# BW1098OAK_IMX378.net
KiCad netlist of a schematic drawn in Altium Designer
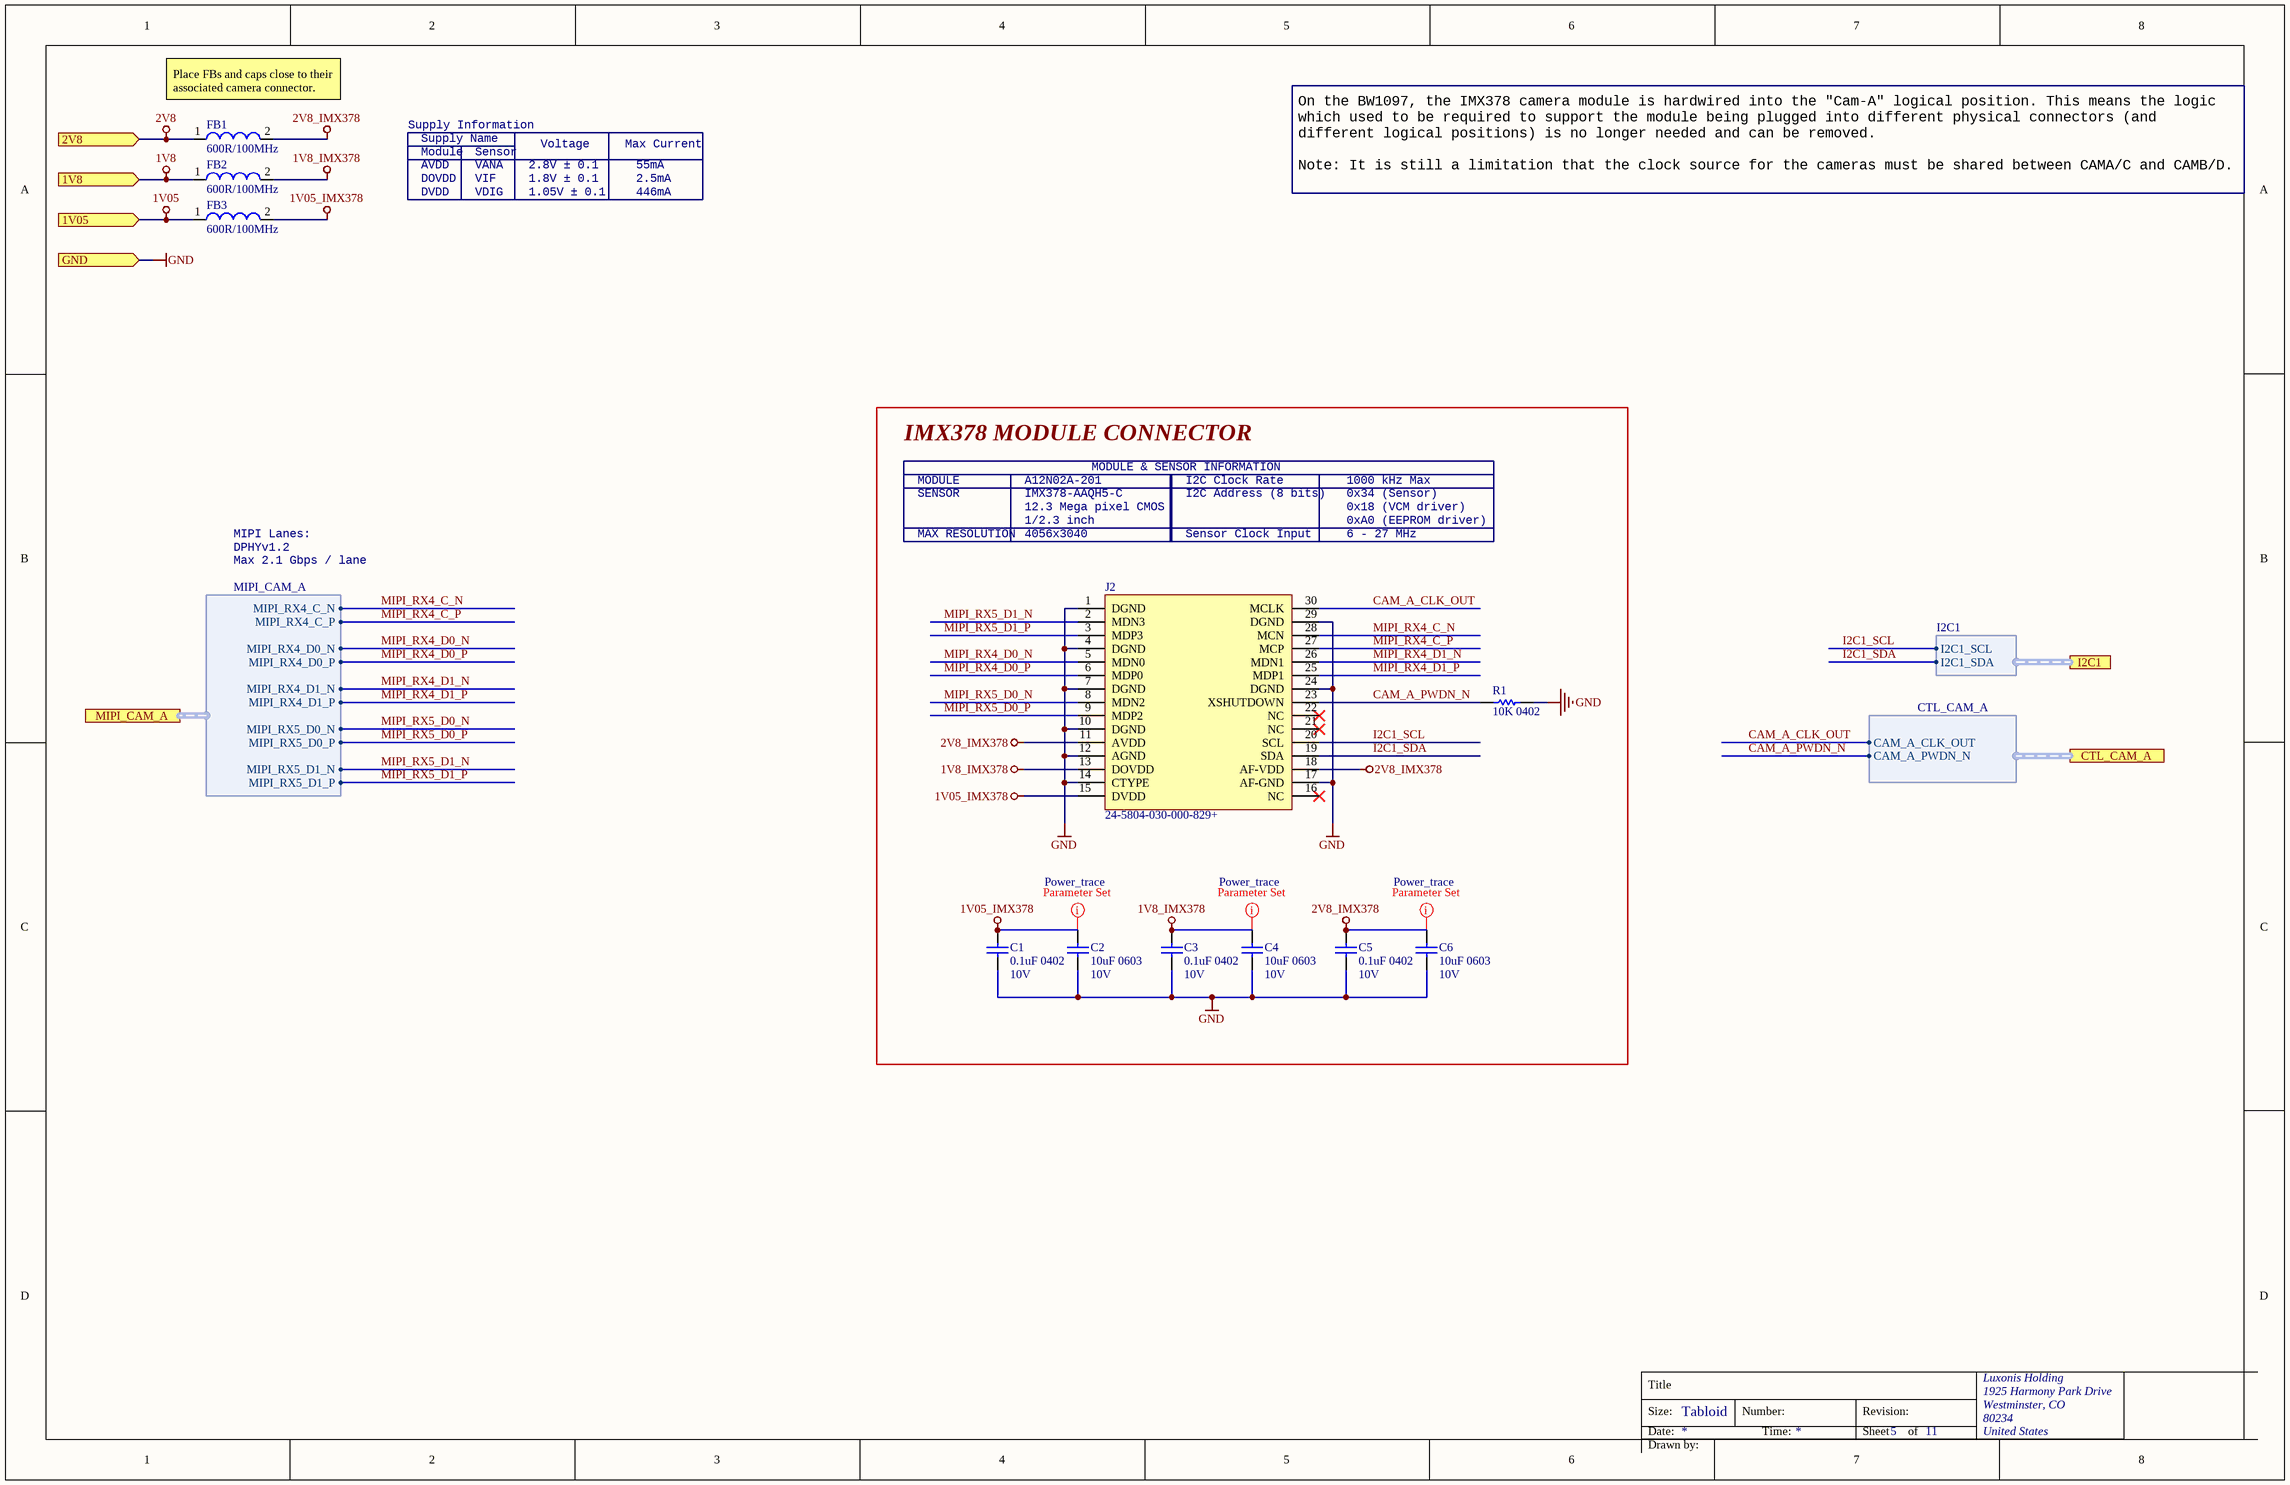
[diagram p0: BW1098OAK_IMX378.SchDoc]

(export (version "E")
  (design (tool "Eeschema 10.0.6"))
  (components
    (comp (ref "C1")
      (value "0.1uF 0402")
      (footprint "CAP_Altium_Vault_Generic:CAPC0402(1005)70_L")
      (description "CAP CER 0.1UF 10V X7R 0402 5%")
      (fields (field (name "TOLERANCE") "5%") (field (name "VOLTAGE RATING") "10V"))
      (libsource (lib "LuxonisMaster") (part "GRM155R71A104JA01D"))
    )
    (comp (ref "C2")
      (value "10uF 0603")
      (footprint "CAP_Altium_Vault_Generic:CAPC0603(1608)100_L")
      (description "CAP CER 10UF 10V X5R 0603 20%")
      (fields (field (name "TOLERANCE") "20%") (field (name "VOLTAGE RATING") "10V"))
      (libsource (lib "LuxonisMaster") (part "GRM188R61A106ME69D"))
    )
    (comp (ref "C3")
      (value "0.1uF 0402")
      (footprint "CAP_Altium_Vault_Generic:CAPC0402(1005)70_L")
      (description "CAP CER 0.1UF 10V X7R 0402 5%")
      (fields (field (name "TOLERANCE") "5%") (field (name "VOLTAGE RATING") "10V"))
      (libsource (lib "LuxonisMaster") (part "GRM155R71A104JA01D"))
    )
    (comp (ref "C4")
      (value "10uF 0603")
      (footprint "CAP_Altium_Vault_Generic:CAPC0603(1608)100_L")
      (description "CAP CER 10UF 10V X5R 0603 20%")
      (fields (field (name "TOLERANCE") "20%") (field (name "VOLTAGE RATING") "10V"))
      (libsource (lib "LuxonisMaster") (part "GRM188R61A106ME69D"))
    )
    (comp (ref "C5")
      (value "0.1uF 0402")
      (footprint "CAP_Altium_Vault_Generic:CAPC0402(1005)70_L")
      (description "CAP CER 0.1UF 10V X7R 0402 5%")
      (fields (field (name "TOLERANCE") "5%") (field (name "VOLTAGE RATING") "10V"))
      (libsource (lib "LuxonisMaster") (part "GRM155R71A104JA01D"))
    )
    (comp (ref "C6")
      (value "10uF 0603")
      (footprint "CAP_Altium_Vault_Generic:CAPC0603(1608)100_L")
      (description "CAP CER 10UF 10V X5R 0603 20%")
      (fields (field (name "TOLERANCE") "20%") (field (name "VOLTAGE RATING") "10V"))
      (libsource (lib "LuxonisMaster") (part "GRM188R61A106ME69D"))
    )
    (comp (ref "FB1")
      (value "600R/100MHz")
      (footprint "LuxonisMaster:2508056017Y2")
      (description "FERRITE BEAD, 0.1OHM, 2A, 0805, 600R/100MHz")
      (fields (field (name "TOLERANCE") "25%"))
      (libsource (lib "LuxonisMaster") (part "2508056017Y2"))
    )
    (comp (ref "FB2")
      (value "600R/100MHz")
      (footprint "LuxonisMaster:2508056017Y2")
      (description "FERRITE BEAD, 0.1OHM, 2A, 0805, 600R/100MHz")
      (fields (field (name "TOLERANCE") "25%"))
      (libsource (lib "LuxonisMaster") (part "2508056017Y2"))
    )
    (comp (ref "FB3")
      (value "600R/100MHz")
      (footprint "LuxonisMaster:2508056017Y2")
      (description "FERRITE BEAD, 0.1OHM, 2A, 0805, 600R/100MHz")
      (fields (field (name "TOLERANCE") "25%"))
      (libsource (lib "LuxonisMaster") (part "2508056017Y2"))
    )
    (comp (ref "J2")
      (value "24-5804-030-000-829+")
      (footprint "BW1098OBC_R3M1E3:A12N02A-201_1.6mmbrd_MatedModule")
      (description "CONN Series 5804 board to board 0.4mm pitch 30 way connector")
      (libsource (lib "BW1098OAK_R0M0E0") (part "A12N02A-201_Connector_(1.6mm_brd)"))
    )
    (comp (ref "R1")
      (value "10K 0402")
      (footprint "RES_Altium_Vault_Generic:RESC0402(1005)_L")
      (fields (field (name "TOLERANCE") "1%"))
      (libsource (lib "LuxonisMaster") (part "RC0402FR-1310KL"))
    )
  )
  (nets
    (net (code "4") (name "/CAM_A_CLK_OUT") (class "Default")
      (node (ref "J2") (pin "30") (pinfunction "MCLK_30") (pintype "passive"))
    )
    (net (code "5") (name "/CAM_A_PWDN_N") (class "Default")
      (node (ref "J2") (pin "23") (pinfunction "XSHUTDOWN_23") (pintype "passive"))
      (node (ref "R1") (pin "1") (pinfunction "1_1") (pintype "passive"))
    )
    (net (code "6") (name "/I2C1_SCL") (class "Default")
      (node (ref "J2") (pin "20") (pinfunction "SCL_20") (pintype "passive"))
    )
    (net (code "7") (name "/I2C1_SDA") (class "Default")
      (node (ref "J2") (pin "19") (pinfunction "SDA_19") (pintype "passive"))
    )
    (net (code "8") (name "/MIPI_RX4_C_N") (class "Default")
      (node (ref "J2") (pin "28") (pinfunction "MCN_28") (pintype "passive"))
    )
    (net (code "9") (name "/MIPI_RX4_C_P") (class "Default")
      (node (ref "J2") (pin "27") (pinfunction "MCP_27") (pintype "passive"))
    )
    (net (code "10") (name "/MIPI_RX4_D0_N") (class "Default")
      (node (ref "J2") (pin "5") (pinfunction "MDN0_5") (pintype "passive"))
    )
    (net (code "11") (name "/MIPI_RX4_D0_P") (class "Default")
      (node (ref "J2") (pin "6") (pinfunction "MDP0_6") (pintype "passive"))
    )
    (net (code "12") (name "/MIPI_RX4_D1_N") (class "Default")
      (node (ref "J2") (pin "26") (pinfunction "MDN1_26") (pintype "passive"))
    )
    (net (code "13") (name "/MIPI_RX4_D1_P") (class "Default")
      (node (ref "J2") (pin "25") (pinfunction "MDP1_25") (pintype "passive"))
    )
    (net (code "14") (name "/MIPI_RX5_D0_N") (class "Default")
      (node (ref "J2") (pin "8") (pinfunction "MDN2_8") (pintype "passive"))
    )
    (net (code "15") (name "/MIPI_RX5_D0_P") (class "Default")
      (node (ref "J2") (pin "9") (pinfunction "MDP2_9") (pintype "passive"))
    )
    (net (code "16") (name "/MIPI_RX5_D1_N") (class "Default")
      (node (ref "J2") (pin "2") (pinfunction "MDN3_2") (pintype "passive"))
    )
    (net (code "17") (name "/MIPI_RX5_D1_P") (class "Default")
      (node (ref "J2") (pin "3") (pinfunction "MDP3_3") (pintype "passive"))
    )
    (net (code "21") (name "1V05") (class "Default")
      (node (ref "FB3") (pin "1") (pinfunction "1_1") (pintype "passive"))
    )
    (net (code "22") (name "1V05_IMX378") (class "Default")
      (node (ref "C1") (pin "2") (pinfunction "2_2") (pintype "passive"))
      (node (ref "C2") (pin "2") (pinfunction "2_2") (pintype "passive"))
      (node (ref "FB3") (pin "2") (pinfunction "2_2") (pintype "passive"))
      (node (ref "J2") (pin "15") (pinfunction "DVDD_15") (pintype "passive"))
    )
    (net (code "23") (name "1V8") (class "Default")
      (node (ref "FB2") (pin "1") (pinfunction "1_1") (pintype "passive"))
    )
    (net (code "24") (name "1V8_IMX378") (class "Default")
      (node (ref "C3") (pin "2") (pinfunction "2_2") (pintype "passive"))
      (node (ref "C4") (pin "2") (pinfunction "2_2") (pintype "passive"))
      (node (ref "FB2") (pin "2") (pinfunction "2_2") (pintype "passive"))
      (node (ref "J2") (pin "13") (pinfunction "DOVDD_13") (pintype "passive"))
    )
    (net (code "25") (name "2V8") (class "Default")
      (node (ref "FB1") (pin "1") (pinfunction "1_1") (pintype "passive"))
    )
    (net (code "26") (name "2V8_IMX378") (class "Default")
      (node (ref "C5") (pin "2") (pinfunction "2_2") (pintype "passive"))
      (node (ref "C6") (pin "2") (pinfunction "2_2") (pintype "passive"))
      (node (ref "FB1") (pin "2") (pinfunction "2_2") (pintype "passive"))
      (node (ref "J2") (pin "11") (pinfunction "AVDD_11") (pintype "passive"))
      (node (ref "J2") (pin "18") (pinfunction "AF-VDD_18") (pintype "passive"))
    )
    (net (code "27") (name "GND") (class "Default")
      (node (ref "C1") (pin "1") (pinfunction "1_1") (pintype "passive"))
      (node (ref "C2") (pin "1") (pinfunction "1_1") (pintype "passive"))
      (node (ref "C3") (pin "1") (pinfunction "1_1") (pintype "passive"))
      (node (ref "C4") (pin "1") (pinfunction "1_1") (pintype "passive"))
      (node (ref "C5") (pin "1") (pinfunction "1_1") (pintype "passive"))
      (node (ref "C6") (pin "1") (pinfunction "1_1") (pintype "passive"))
      (node (ref "J2") (pin "1") (pinfunction "DGND_1") (pintype "passive"))
      (node (ref "J2") (pin "10") (pinfunction "DGND_10") (pintype "passive"))
      (node (ref "J2") (pin "12") (pinfunction "AGND_12") (pintype "passive"))
      (node (ref "J2") (pin "14") (pinfunction "CTYPE_14") (pintype "passive"))
      (node (ref "J2") (pin "17") (pinfunction "AF-GND_17") (pintype "passive"))
      (node (ref "J2") (pin "24") (pinfunction "DGND_24") (pintype "passive"))
      (node (ref "J2") (pin "29") (pinfunction "DGND_29") (pintype "passive"))
      (node (ref "J2") (pin "4") (pinfunction "DGND_4") (pintype "passive"))
      (node (ref "J2") (pin "7") (pinfunction "DGND_7") (pintype "passive"))
      (node (ref "R1") (pin "2") (pinfunction "2_2") (pintype "passive"))
    )
    (net (code "28") (name "unconnected-(J2-NC-Pad16)") (class "Default")
      (node (ref "J2") (pin "16") (pinfunction "NC_16") (pintype "passive+no_connect"))
    )
    (net (code "29") (name "unconnected-(J2-NC-Pad21)") (class "Default")
      (node (ref "J2") (pin "21") (pinfunction "NC_21") (pintype "passive+no_connect"))
    )
    (net (code "30") (name "unconnected-(J2-NC-Pad22)") (class "Default")
      (node (ref "J2") (pin "22") (pinfunction "NC_22") (pintype "passive+no_connect"))
    )
  )
)
